# VREG_RT9166-25PVL.net
KiCad netlist of a schematic drawn in Altium Designer
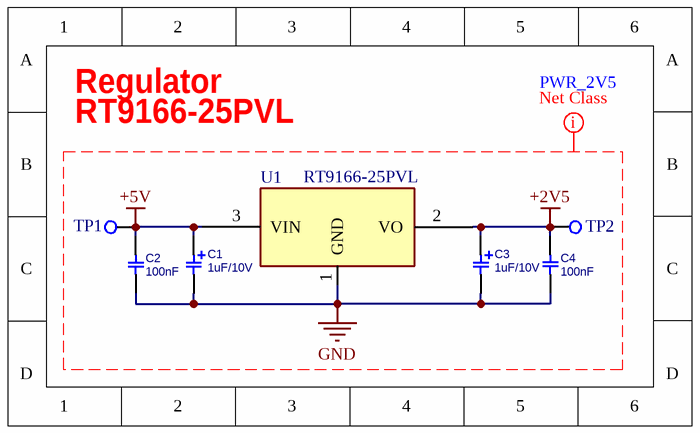
[diagram p0: VREG RT9166-25PVL.SchDoc]

(export (version "E")
  (design (tool "Eeschema 10.0.6"))
  (components
    (comp (ref "C1")
      (value "1uF/10V")
      (footprint "C_TN_A")
      (description "CAP, SMD, TAN")
      (libsource (lib "PW Components 97_492") (part "CAP_SMD_TAN"))
    )
    (comp (ref "C2")
      (value "100nF")
      (footprint "C0603S")
      (description "CAP, SMD, MLCC")
      (fields (field (name "MANF_P#") "MANF_PART#") (field (name "MANF") "Murata"))
      (libsource (lib "Passive") (part "CAP_SMD_MLCC"))
    )
    (comp (ref "C3")
      (value "1uF/10V")
      (footprint "C_TN_A")
      (description "CAP, SMD, TAN")
      (libsource (lib "PW Components 97_492") (part "CAP_SMD_TAN"))
    )
    (comp (ref "C4")
      (value "100nF")
      (footprint "C0603S")
      (description "CAP, SMD, MLCC")
      (fields (field (name "MANF_P#") "MANF_PART#") (field (name "MANF") "Murata"))
      (libsource (lib "Passive") (part "CAP_SMD_MLCC"))
    )
    (comp (ref "TP1")
      (value "Test Point")
      (footprint "TPSMD_C1")
      (libsource (lib "Passives") (part "Test Point"))
    )
    (comp (ref "TP2")
      (value "Test Point")
      (footprint "TPSMD_C1")
      (libsource (lib "Passives") (part "Test Point"))
    )
    (comp (ref "U1")
      (value "RT9166-25PVL")
      (footprint "SOT23_3")
      (description "REG, Linear, Fixed, 2.5v, 0.3A/0.6A, SOT23")
      (fields (field (name "MANF") "TI"))
      (libsource (lib "PW Components 97_481") (part "VREG_RT9166A-25PVL_SOT23"))
    )
  )
  (nets
    (net (code "1") (name "+2V5") (class "Default")
      (node (ref "C3") (pin "1") (pinfunction "1_1") (pintype "passive"))
      (node (ref "C4") (pin "1") (pinfunction "1_1") (pintype "passive"))
      (node (ref "TP2") (pin "1") (pinfunction "TP_1") (pintype "passive"))
      (node (ref "U1") (pin "2") (pinfunction "VO_2") (pintype "passive"))
    )
    (net (code "2") (name "+5V") (class "Default")
      (node (ref "C1") (pin "1") (pinfunction "1_1") (pintype "passive"))
      (node (ref "C2") (pin "1") (pinfunction "1_1") (pintype "passive"))
      (node (ref "TP1") (pin "1") (pinfunction "TP_1") (pintype "passive"))
      (node (ref "U1") (pin "3") (pinfunction "VIN_3") (pintype "passive"))
    )
    (net (code "3") (name "GND") (class "Default")
      (node (ref "C1") (pin "2") (pinfunction "2_2") (pintype "passive"))
      (node (ref "C2") (pin "2") (pinfunction "2_2") (pintype "passive"))
      (node (ref "C3") (pin "2") (pinfunction "2_2") (pintype "passive"))
      (node (ref "C4") (pin "2") (pinfunction "2_2") (pintype "passive"))
      (node (ref "U1") (pin "1") (pinfunction "GND_1") (pintype "passive"))
    )
  )
)
